# FAL65816_cpua.net
KiCad netlist of a schematic drawn in EAGLE
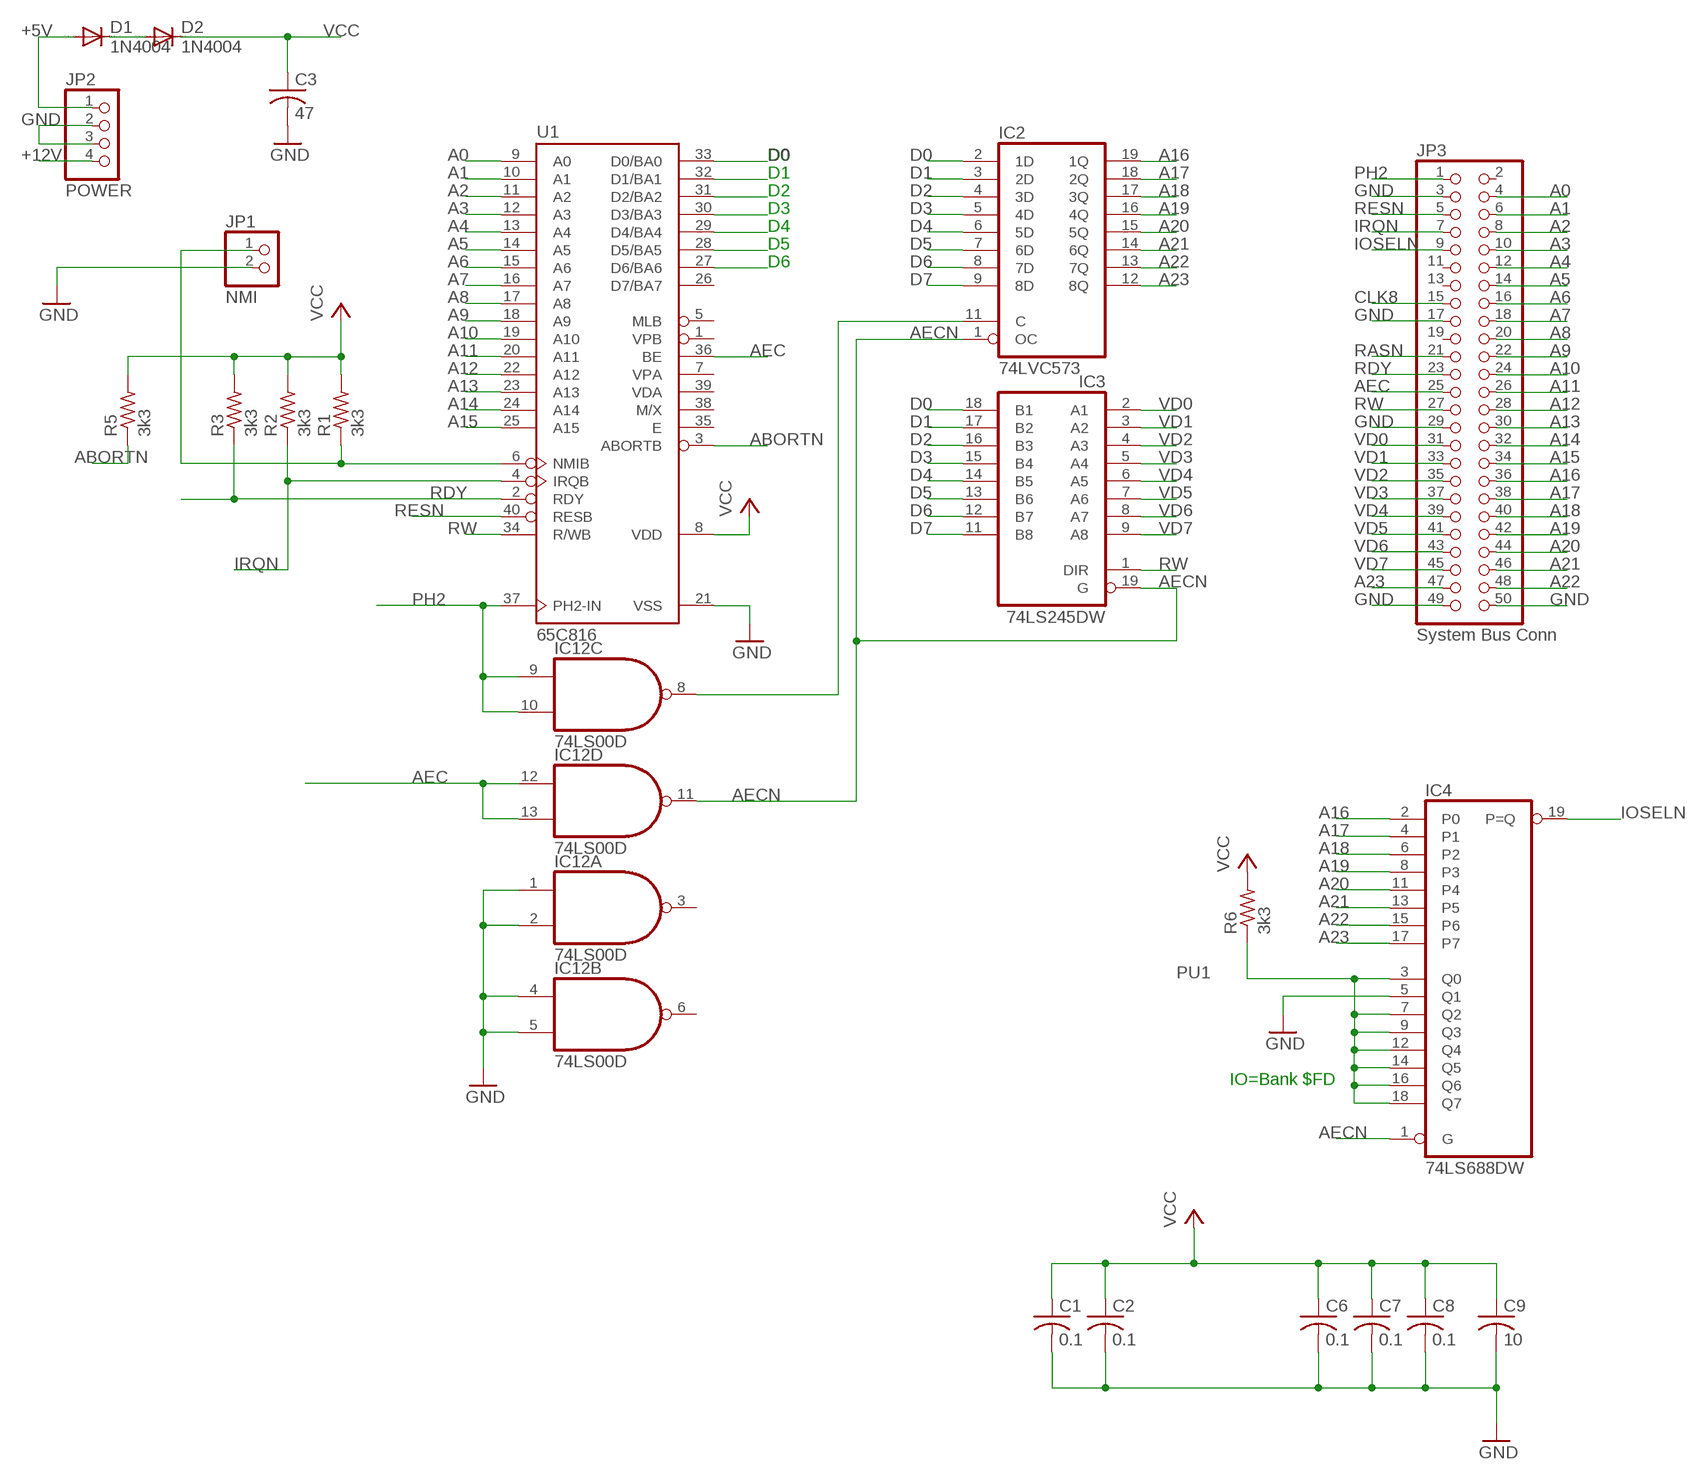
[diagram p0: schematic, sheet 1]

(export (version "E")
  (design (tool "Eeschema 10.0.6"))
  (components
    (comp (ref "C1")
      (value "0.1")
      (footprint "eagle-import:C050-024X044")
      (libsource (lib "eagle-import") (part "C-US050-024X044"))
    )
    (comp (ref "C2")
      (value "0.1")
      (footprint "eagle-import:C050-024X044")
      (libsource (lib "eagle-import") (part "C-US050-024X044"))
    )
    (comp (ref "C3")
      (value "47")
      (footprint "eagle-import:C050-024X044")
      (libsource (lib "eagle-import") (part "C-US050-024X044"))
    )
    (comp (ref "C6")
      (value "0.1")
      (footprint "eagle-import:C050-024X044")
      (libsource (lib "eagle-import") (part "C-US050-024X044"))
    )
    (comp (ref "C7")
      (value "0.1")
      (footprint "eagle-import:C050-024X044")
      (libsource (lib "eagle-import") (part "C-US050-024X044"))
    )
    (comp (ref "C8")
      (value "0.1")
      (footprint "eagle-import:C050-024X044")
      (libsource (lib "eagle-import") (part "C-US050-024X044"))
    )
    (comp (ref "C9")
      (value "10")
      (footprint "eagle-import:C050-024X044")
      (libsource (lib "eagle-import") (part "C-US050-024X044"))
    )
    (comp (ref "D1")
      (value "1N4004")
      (footprint "eagle-import:DO41-10")
      (libsource (lib "eagle-import") (part "1N4004"))
    )
    (comp (ref "D2")
      (value "1N4004")
      (footprint "eagle-import:DO41-10")
      (libsource (lib "eagle-import") (part "1N4004"))
    )
    (comp (ref "IC2")
      (value "74LVC573")
      (footprint "eagle-import:SO20W")
      (libsource (lib "eagle-import") (part "74573LVC"))
    )
    (comp (ref "IC3")
      (value "74LS245DW")
      (footprint "eagle-import:SO20W")
      (libsource (lib "eagle-import") (part "74245DWLS"))
    )
    (comp (ref "IC4")
      (value "74LS688DW")
      (footprint "eagle-import:SO20W")
      (libsource (lib "eagle-import") (part "74688DWLS"))
    )
    (comp (ref "IC12")
      (value "74LS00D")
      (footprint "eagle-import:SO14")
      (libsource (lib "eagle-import") (part "7400DLS"))
    )
    (comp (ref "JP1")
      (value "NMI")
      (footprint "eagle-import:1X02")
      (libsource (lib "eagle-import") (part "PINHD-1X2"))
    )
    (comp (ref "JP2")
      (value "POWER")
      (footprint "eagle-import:1X04_90")
      (libsource (lib "eagle-import") (part "PINHD-1X4/90"))
    )
    (comp (ref "JP3")
      (value "System Bus Conn")
      (footprint "eagle-import:2X25_90")
      (libsource (lib "eagle-import") (part "PINHD-2X25/90"))
    )
    (comp (ref "R1")
      (value "3k3")
      (footprint "eagle-import:0207_10")
      (libsource (lib "eagle-import") (part "R-US_0207/10"))
    )
    (comp (ref "R2")
      (value "3k3")
      (footprint "eagle-import:0207_10")
      (libsource (lib "eagle-import") (part "R-US_0207/10"))
    )
    (comp (ref "R3")
      (value "3k3")
      (footprint "eagle-import:0207_10")
      (libsource (lib "eagle-import") (part "R-US_0207/10"))
    )
    (comp (ref "R5")
      (value "3k3")
      (footprint "eagle-import:0207_10")
      (libsource (lib "eagle-import") (part "R-US_0207/10"))
    )
    (comp (ref "R6")
      (value "3k3")
      (footprint "eagle-import:0204_7")
      (libsource (lib "eagle-import") (part "R-US_0204/7"))
    )
    (comp (ref "U1")
      (value "65C816")
      (footprint "eagle-import:DIP-40")
      (libsource (lib "eagle-import") (part "W65C816SP"))
    )
  )
  (nets
    (net (code "1") (name "/+5V") (class "Default")
      (node (ref "D1") (pin "A") (pinfunction "A_A") (pintype "passive"))
      (node (ref "JP2") (pin "1") (pinfunction "1_1") (pintype "passive"))
    )
    (net (code "2") (name "/+12V") (class "Default")
      (node (ref "JP2") (pin "4") (pinfunction "4_4") (pintype "passive"))
    )
    (net (code "3") (name "/A0") (class "Default")
      (node (ref "JP3") (pin "4") (pinfunction "4_4") (pintype "passive"))
      (node (ref "U1") (pin "9") (pinfunction "A0_9") (pintype "bidirectional"))
    )
    (net (code "4") (name "/A1") (class "Default")
      (node (ref "JP3") (pin "6") (pinfunction "6_6") (pintype "passive"))
      (node (ref "U1") (pin "10") (pinfunction "A1_10") (pintype "bidirectional"))
    )
    (net (code "5") (name "/A2") (class "Default")
      (node (ref "JP3") (pin "8") (pinfunction "8_8") (pintype "passive"))
      (node (ref "U1") (pin "11") (pinfunction "A2_11") (pintype "bidirectional"))
    )
    (net (code "6") (name "/A3") (class "Default")
      (node (ref "JP3") (pin "10") (pinfunction "10_10") (pintype "passive"))
      (node (ref "U1") (pin "12") (pinfunction "A3_12") (pintype "bidirectional"))
    )
    (net (code "7") (name "/A4") (class "Default")
      (node (ref "JP3") (pin "12") (pinfunction "12_12") (pintype "passive"))
      (node (ref "U1") (pin "13") (pinfunction "A4_13") (pintype "bidirectional"))
    )
    (net (code "8") (name "/A5") (class "Default")
      (node (ref "JP3") (pin "14") (pinfunction "14_14") (pintype "passive"))
      (node (ref "U1") (pin "14") (pinfunction "A5_14") (pintype "bidirectional"))
    )
    (net (code "9") (name "/A6") (class "Default")
      (node (ref "JP3") (pin "16") (pinfunction "16_16") (pintype "passive"))
      (node (ref "U1") (pin "15") (pinfunction "A6_15") (pintype "bidirectional"))
    )
    (net (code "10") (name "/A7") (class "Default")
      (node (ref "JP3") (pin "18") (pinfunction "18_18") (pintype "passive"))
      (node (ref "U1") (pin "16") (pinfunction "A7_16") (pintype "bidirectional"))
    )
    (net (code "11") (name "/A8") (class "Default")
      (node (ref "JP3") (pin "20") (pinfunction "20_20") (pintype "passive"))
      (node (ref "U1") (pin "17") (pinfunction "A8_17") (pintype "bidirectional"))
    )
    (net (code "12") (name "/A9") (class "Default")
      (node (ref "JP3") (pin "22") (pinfunction "22_22") (pintype "passive"))
      (node (ref "U1") (pin "18") (pinfunction "A9_18") (pintype "bidirectional"))
    )
    (net (code "13") (name "/A10") (class "Default")
      (node (ref "JP3") (pin "24") (pinfunction "24_24") (pintype "passive"))
      (node (ref "U1") (pin "19") (pinfunction "A10_19") (pintype "bidirectional"))
    )
    (net (code "14") (name "/A11") (class "Default")
      (node (ref "JP3") (pin "26") (pinfunction "26_26") (pintype "passive"))
      (node (ref "U1") (pin "20") (pinfunction "A11_20") (pintype "bidirectional"))
    )
    (net (code "15") (name "/A12") (class "Default")
      (node (ref "JP3") (pin "28") (pinfunction "28_28") (pintype "passive"))
      (node (ref "U1") (pin "22") (pinfunction "A12_22") (pintype "bidirectional"))
    )
    (net (code "16") (name "/A13") (class "Default")
      (node (ref "JP3") (pin "30") (pinfunction "30_30") (pintype "passive"))
      (node (ref "U1") (pin "23") (pinfunction "A13_23") (pintype "bidirectional"))
    )
    (net (code "17") (name "/A14") (class "Default")
      (node (ref "JP3") (pin "32") (pinfunction "32_32") (pintype "passive"))
      (node (ref "U1") (pin "24") (pinfunction "A14_24") (pintype "bidirectional"))
    )
    (net (code "18") (name "/A15") (class "Default")
      (node (ref "JP3") (pin "34") (pinfunction "34_34") (pintype "passive"))
      (node (ref "U1") (pin "25") (pinfunction "A15_25") (pintype "bidirectional"))
    )
    (net (code "19") (name "/A16") (class "Default")
      (node (ref "IC2") (pin "19") (pinfunction "1Q_19") (pintype "tri_state"))
      (node (ref "IC4") (pin "2") (pinfunction "P0_2") (pintype "input"))
      (node (ref "JP3") (pin "36") (pinfunction "36_36") (pintype "passive"))
    )
    (net (code "20") (name "/A17") (class "Default")
      (node (ref "IC2") (pin "18") (pinfunction "2Q_18") (pintype "tri_state"))
      (node (ref "IC4") (pin "4") (pinfunction "P1_4") (pintype "input"))
      (node (ref "JP3") (pin "38") (pinfunction "38_38") (pintype "passive"))
    )
    (net (code "21") (name "/A18") (class "Default")
      (node (ref "IC2") (pin "17") (pinfunction "3Q_17") (pintype "tri_state"))
      (node (ref "IC4") (pin "6") (pinfunction "P2_6") (pintype "input"))
      (node (ref "JP3") (pin "40") (pinfunction "40_40") (pintype "passive"))
    )
    (net (code "22") (name "/A19") (class "Default")
      (node (ref "IC2") (pin "16") (pinfunction "4Q_16") (pintype "tri_state"))
      (node (ref "IC4") (pin "8") (pinfunction "P3_8") (pintype "input"))
      (node (ref "JP3") (pin "42") (pinfunction "42_42") (pintype "passive"))
    )
    (net (code "23") (name "/A20") (class "Default")
      (node (ref "IC2") (pin "15") (pinfunction "5Q_15") (pintype "tri_state"))
      (node (ref "IC4") (pin "11") (pinfunction "P4_11") (pintype "input"))
      (node (ref "JP3") (pin "44") (pinfunction "44_44") (pintype "passive"))
    )
    (net (code "24") (name "/A21") (class "Default")
      (node (ref "IC2") (pin "14") (pinfunction "6Q_14") (pintype "tri_state"))
      (node (ref "IC4") (pin "13") (pinfunction "P5_13") (pintype "input"))
      (node (ref "JP3") (pin "46") (pinfunction "46_46") (pintype "passive"))
    )
    (net (code "25") (name "/A22") (class "Default")
      (node (ref "IC2") (pin "13") (pinfunction "7Q_13") (pintype "tri_state"))
      (node (ref "IC4") (pin "15") (pinfunction "P6_15") (pintype "input"))
      (node (ref "JP3") (pin "48") (pinfunction "48_48") (pintype "passive"))
    )
    (net (code "26") (name "/A23") (class "Default")
      (node (ref "IC2") (pin "12") (pinfunction "8Q_12") (pintype "tri_state"))
      (node (ref "IC4") (pin "17") (pinfunction "P7_17") (pintype "input"))
      (node (ref "JP3") (pin "47") (pinfunction "47_47") (pintype "passive"))
    )
    (net (code "27") (name "/ABORTN") (class "Default")
      (node (ref "R5") (pin "1") (pinfunction "1_1") (pintype "passive"))
      (node (ref "U1") (pin "3") (pinfunction "ABORTB_3") (pintype "input"))
    )
    (net (code "28") (name "/AEC") (class "Default")
      (node (ref "IC12") (pin "12") (pinfunction "I0_12") (pintype "input"))
      (node (ref "IC12") (pin "13") (pinfunction "I1_13") (pintype "input"))
      (node (ref "JP3") (pin "25") (pinfunction "25_25") (pintype "passive"))
      (node (ref "U1") (pin "36") (pinfunction "BE_36") (pintype "input"))
    )
    (net (code "29") (name "/AECN") (class "Default")
      (node (ref "IC12") (pin "11") (pinfunction "O_11") (pintype "output"))
      (node (ref "IC2") (pin "1") (pinfunction "OC_1") (pintype "input"))
      (node (ref "IC3") (pin "19") (pinfunction "G_19") (pintype "input"))
      (node (ref "IC4") (pin "1") (pinfunction "G_1") (pintype "input"))
    )
    (net (code "30") (name "/CLK8") (class "Default")
      (node (ref "JP3") (pin "15") (pinfunction "15_15") (pintype "passive"))
    )
    (net (code "31") (name "/D0") (class "Default")
      (node (ref "IC2") (pin "2") (pinfunction "1D_2") (pintype "input"))
      (node (ref "IC3") (pin "18") (pinfunction "B1_18") (pintype "bidirectional"))
      (node (ref "U1") (pin "33") (pinfunction "D0/BA0_33") (pintype "bidirectional"))
    )
    (net (code "32") (name "/D1") (class "Default")
      (node (ref "IC2") (pin "3") (pinfunction "2D_3") (pintype "input"))
      (node (ref "IC3") (pin "17") (pinfunction "B2_17") (pintype "bidirectional"))
      (node (ref "U1") (pin "32") (pinfunction "D1/BA1_32") (pintype "bidirectional"))
    )
    (net (code "33") (name "/D2") (class "Default")
      (node (ref "IC2") (pin "4") (pinfunction "3D_4") (pintype "input"))
      (node (ref "IC3") (pin "16") (pinfunction "B3_16") (pintype "bidirectional"))
      (node (ref "U1") (pin "31") (pinfunction "D2/BA2_31") (pintype "bidirectional"))
    )
    (net (code "34") (name "/D3") (class "Default")
      (node (ref "IC2") (pin "5") (pinfunction "4D_5") (pintype "input"))
      (node (ref "IC3") (pin "15") (pinfunction "B4_15") (pintype "bidirectional"))
      (node (ref "U1") (pin "30") (pinfunction "D3/BA3_30") (pintype "bidirectional"))
    )
    (net (code "35") (name "/D4") (class "Default")
      (node (ref "IC2") (pin "6") (pinfunction "5D_6") (pintype "input"))
      (node (ref "IC3") (pin "14") (pinfunction "B5_14") (pintype "bidirectional"))
      (node (ref "U1") (pin "29") (pinfunction "D4/BA4_29") (pintype "bidirectional"))
    )
    (net (code "36") (name "/D5") (class "Default")
      (node (ref "IC2") (pin "7") (pinfunction "6D_7") (pintype "input"))
      (node (ref "IC3") (pin "13") (pinfunction "B6_13") (pintype "bidirectional"))
      (node (ref "U1") (pin "28") (pinfunction "D5/BA5_28") (pintype "bidirectional"))
    )
    (net (code "37") (name "/D6") (class "Default")
      (node (ref "IC2") (pin "8") (pinfunction "7D_8") (pintype "input"))
      (node (ref "IC3") (pin "12") (pinfunction "B7_12") (pintype "bidirectional"))
      (node (ref "U1") (pin "27") (pinfunction "D6/BA6_27") (pintype "bidirectional"))
    )
    (net (code "38") (name "/D7") (class "Default")
      (node (ref "IC2") (pin "9") (pinfunction "8D_9") (pintype "input"))
      (node (ref "IC3") (pin "11") (pinfunction "B8_11") (pintype "bidirectional"))
    )
    (net (code "39") (name "/IOSELN") (class "Default")
      (node (ref "IC4") (pin "19") (pinfunction "P=Q_19") (pintype "output"))
      (node (ref "JP3") (pin "9") (pinfunction "9_9") (pintype "passive"))
    )
    (net (code "40") (name "/IRQN") (class "Default")
      (node (ref "JP3") (pin "7") (pinfunction "7_7") (pintype "passive"))
      (node (ref "R2") (pin "1") (pinfunction "1_1") (pintype "passive"))
      (node (ref "U1") (pin "4") (pinfunction "IRQB_4") (pintype "input"))
    )
    (net (code "41") (name "/PH2") (class "Default")
      (node (ref "IC12") (pin "10") (pinfunction "I1_10") (pintype "input"))
      (node (ref "IC12") (pin "9") (pinfunction "I0_9") (pintype "input"))
      (node (ref "JP3") (pin "1") (pinfunction "1_1") (pintype "passive"))
      (node (ref "U1") (pin "37") (pinfunction "PH2-IN_37") (pintype "input"))
    )
    (net (code "42") (name "/PU1") (class "Default")
      (node (ref "IC4") (pin "12") (pinfunction "Q4_12") (pintype "input"))
      (node (ref "IC4") (pin "14") (pinfunction "Q5_14") (pintype "input"))
      (node (ref "IC4") (pin "16") (pinfunction "Q6_16") (pintype "input"))
      (node (ref "IC4") (pin "18") (pinfunction "Q7_18") (pintype "input"))
      (node (ref "IC4") (pin "3") (pinfunction "Q0_3") (pintype "input"))
      (node (ref "IC4") (pin "7") (pinfunction "Q2_7") (pintype "input"))
      (node (ref "IC4") (pin "9") (pinfunction "Q3_9") (pintype "input"))
      (node (ref "R6") (pin "1") (pinfunction "1_1") (pintype "passive"))
    )
    (net (code "43") (name "/RASN") (class "Default")
      (node (ref "JP3") (pin "21") (pinfunction "21_21") (pintype "passive"))
    )
    (net (code "44") (name "/RDY") (class "Default")
      (node (ref "JP3") (pin "23") (pinfunction "23_23") (pintype "passive"))
      (node (ref "R3") (pin "1") (pinfunction "1_1") (pintype "passive"))
      (node (ref "U1") (pin "2") (pinfunction "RDY_2") (pintype "bidirectional"))
    )
    (net (code "45") (name "/RESN") (class "Default")
      (node (ref "JP3") (pin "5") (pinfunction "5_5") (pintype "passive"))
      (node (ref "U1") (pin "40") (pinfunction "RESB_40") (pintype "input"))
    )
    (net (code "46") (name "/RW") (class "Default")
      (node (ref "IC3") (pin "1") (pinfunction "DIR_1") (pintype "input"))
      (node (ref "JP3") (pin "27") (pinfunction "27_27") (pintype "passive"))
      (node (ref "U1") (pin "34") (pinfunction "R/WB_34") (pintype "output"))
    )
    (net (code "47") (name "/VD0") (class "Default")
      (node (ref "IC3") (pin "2") (pinfunction "A1_2") (pintype "bidirectional"))
      (node (ref "JP3") (pin "31") (pinfunction "31_31") (pintype "passive"))
    )
    (net (code "48") (name "/VD1") (class "Default")
      (node (ref "IC3") (pin "3") (pinfunction "A2_3") (pintype "bidirectional"))
      (node (ref "JP3") (pin "33") (pinfunction "33_33") (pintype "passive"))
    )
    (net (code "49") (name "/VD2") (class "Default")
      (node (ref "IC3") (pin "4") (pinfunction "A3_4") (pintype "bidirectional"))
      (node (ref "JP3") (pin "35") (pinfunction "35_35") (pintype "passive"))
    )
    (net (code "50") (name "/VD3") (class "Default")
      (node (ref "IC3") (pin "5") (pinfunction "A4_5") (pintype "bidirectional"))
      (node (ref "JP3") (pin "37") (pinfunction "37_37") (pintype "passive"))
    )
    (net (code "51") (name "/VD4") (class "Default")
      (node (ref "IC3") (pin "6") (pinfunction "A5_6") (pintype "bidirectional"))
      (node (ref "JP3") (pin "39") (pinfunction "39_39") (pintype "passive"))
    )
    (net (code "52") (name "/VD5") (class "Default")
      (node (ref "IC3") (pin "7") (pinfunction "A6_7") (pintype "bidirectional"))
      (node (ref "JP3") (pin "41") (pinfunction "41_41") (pintype "passive"))
    )
    (net (code "53") (name "/VD6") (class "Default")
      (node (ref "IC3") (pin "8") (pinfunction "A7_8") (pintype "bidirectional"))
      (node (ref "JP3") (pin "43") (pinfunction "43_43") (pintype "passive"))
    )
    (net (code "54") (name "/VD7") (class "Default")
      (node (ref "IC3") (pin "9") (pinfunction "A8_9") (pintype "bidirectional"))
      (node (ref "JP3") (pin "45") (pinfunction "45_45") (pintype "passive"))
    )
    (net (code "55") (name "GND") (class "Default")
      (node (ref "C1") (pin "2") (pinfunction "2_2") (pintype "passive"))
      (node (ref "C2") (pin "2") (pinfunction "2_2") (pintype "passive"))
      (node (ref "C3") (pin "2") (pinfunction "2_2") (pintype "passive"))
      (node (ref "C6") (pin "2") (pinfunction "2_2") (pintype "passive"))
      (node (ref "C7") (pin "2") (pinfunction "2_2") (pintype "passive"))
      (node (ref "C8") (pin "2") (pinfunction "2_2") (pintype "passive"))
      (node (ref "C9") (pin "2") (pinfunction "2_2") (pintype "passive"))
      (node (ref "IC12") (pin "1") (pinfunction "I0_1") (pintype "input"))
      (node (ref "IC12") (pin "2") (pinfunction "I1_2") (pintype "input"))
      (node (ref "IC12") (pin "4") (pinfunction "I0_4") (pintype "input"))
      (node (ref "IC12") (pin "5") (pinfunction "I1_5") (pintype "input"))
      (node (ref "IC4") (pin "5") (pinfunction "Q1_5") (pintype "input"))
      (node (ref "JP1") (pin "2") (pinfunction "2_2") (pintype "passive"))
      (node (ref "JP2") (pin "2") (pinfunction "2_2") (pintype "passive"))
      (node (ref "JP2") (pin "3") (pinfunction "3_3") (pintype "passive"))
      (node (ref "JP3") (pin "17") (pinfunction "17_17") (pintype "passive"))
      (node (ref "JP3") (pin "29") (pinfunction "29_29") (pintype "passive"))
      (node (ref "JP3") (pin "3") (pinfunction "3_3") (pintype "passive"))
      (node (ref "JP3") (pin "49") (pinfunction "49_49") (pintype "passive"))
      (node (ref "JP3") (pin "50") (pinfunction "50_50") (pintype "passive"))
      (node (ref "U1") (pin "21") (pinfunction "VSS_21") (pintype "power_in"))
    )
    (net (code "56") (name "Net-(D1-PadC)") (class "Default")
      (node (ref "D1") (pin "C") (pinfunction "C_C") (pintype "passive"))
      (node (ref "D2") (pin "A") (pinfunction "A_A") (pintype "passive"))
    )
    (net (code "57") (name "Net-(IC12C-O)") (class "Default")
      (node (ref "IC12") (pin "8") (pinfunction "O_8") (pintype "output"))
      (node (ref "IC2") (pin "11") (pinfunction "C_11") (pintype "input"))
    )
    (net (code "58") (name "Net-(U1-NMIB)") (class "Default")
      (node (ref "JP1") (pin "1") (pinfunction "1_1") (pintype "passive"))
      (node (ref "R1") (pin "1") (pinfunction "1_1") (pintype "passive"))
      (node (ref "U1") (pin "6") (pinfunction "NMIB_6") (pintype "input"))
    )
    (net (code "59") (name "VCC") (class "Default")
      (node (ref "C1") (pin "1") (pinfunction "1_1") (pintype "passive"))
      (node (ref "C2") (pin "1") (pinfunction "1_1") (pintype "passive"))
      (node (ref "C3") (pin "1") (pinfunction "1_1") (pintype "passive"))
      (node (ref "C6") (pin "1") (pinfunction "1_1") (pintype "passive"))
      (node (ref "C7") (pin "1") (pinfunction "1_1") (pintype "passive"))
      (node (ref "C8") (pin "1") (pinfunction "1_1") (pintype "passive"))
      (node (ref "C9") (pin "1") (pinfunction "1_1") (pintype "passive"))
      (node (ref "D2") (pin "C") (pinfunction "C_C") (pintype "passive"))
      (node (ref "R1") (pin "2") (pinfunction "2_2") (pintype "passive"))
      (node (ref "R2") (pin "2") (pinfunction "2_2") (pintype "passive"))
      (node (ref "R3") (pin "2") (pinfunction "2_2") (pintype "passive"))
      (node (ref "R5") (pin "2") (pinfunction "2_2") (pintype "passive"))
      (node (ref "R6") (pin "2") (pinfunction "2_2") (pintype "passive"))
      (node (ref "U1") (pin "8") (pinfunction "VDD_8") (pintype "power_in"))
    )
    (net (code "60") (name "unconnected-(IC12A-O-Pad3)") (class "Default")
      (node (ref "IC12") (pin "3") (pinfunction "O_3") (pintype "output"))
    )
    (net (code "61") (name "unconnected-(IC12B-O-Pad6)") (class "Default")
      (node (ref "IC12") (pin "6") (pinfunction "O_6") (pintype "output"))
    )
    (net (code "62") (name "unconnected-(JP3-Pad2)") (class "Default")
      (node (ref "JP3") (pin "2") (pinfunction "2_2") (pintype "passive"))
    )
    (net (code "63") (name "unconnected-(JP3-Pad11)") (class "Default")
      (node (ref "JP3") (pin "11") (pinfunction "11_11") (pintype "passive"))
    )
    (net (code "64") (name "unconnected-(JP3-Pad13)") (class "Default")
      (node (ref "JP3") (pin "13") (pinfunction "13_13") (pintype "passive"))
    )
    (net (code "65") (name "unconnected-(JP3-Pad19)") (class "Default")
      (node (ref "JP3") (pin "19") (pinfunction "19_19") (pintype "passive"))
    )
    (net (code "66") (name "unconnected-(U1-D7{slash}BA7-Pad26)") (class "Default")
      (node (ref "U1") (pin "26") (pinfunction "D7/BA7_26") (pintype "bidirectional"))
    )
    (net (code "67") (name "unconnected-(U1-E-Pad35)") (class "Default")
      (node (ref "U1") (pin "35") (pinfunction "E_35") (pintype "output"))
    )
    (net (code "68") (name "unconnected-(U1-MLB-Pad5)") (class "Default")
      (node (ref "U1") (pin "5") (pinfunction "MLB_5") (pintype "output"))
    )
    (net (code "69") (name "unconnected-(U1-M{slash}X-Pad38)") (class "Default")
      (node (ref "U1") (pin "38") (pinfunction "M/X_38") (pintype "output"))
    )
    (net (code "70") (name "unconnected-(U1-VDA-Pad39)") (class "Default")
      (node (ref "U1") (pin "39") (pinfunction "VDA_39") (pintype "output"))
    )
    (net (code "71") (name "unconnected-(U1-VPA-Pad7)") (class "Default")
      (node (ref "U1") (pin "7") (pinfunction "VPA_7") (pintype "output"))
    )
    (net (code "72") (name "unconnected-(U1-VPB-Pad1)") (class "Default")
      (node (ref "U1") (pin "1") (pinfunction "VPB_1") (pintype "output"))
    )
  )
)
